# xduino_1_0.net
KiCad netlist of a schematic drawn in EAGLE
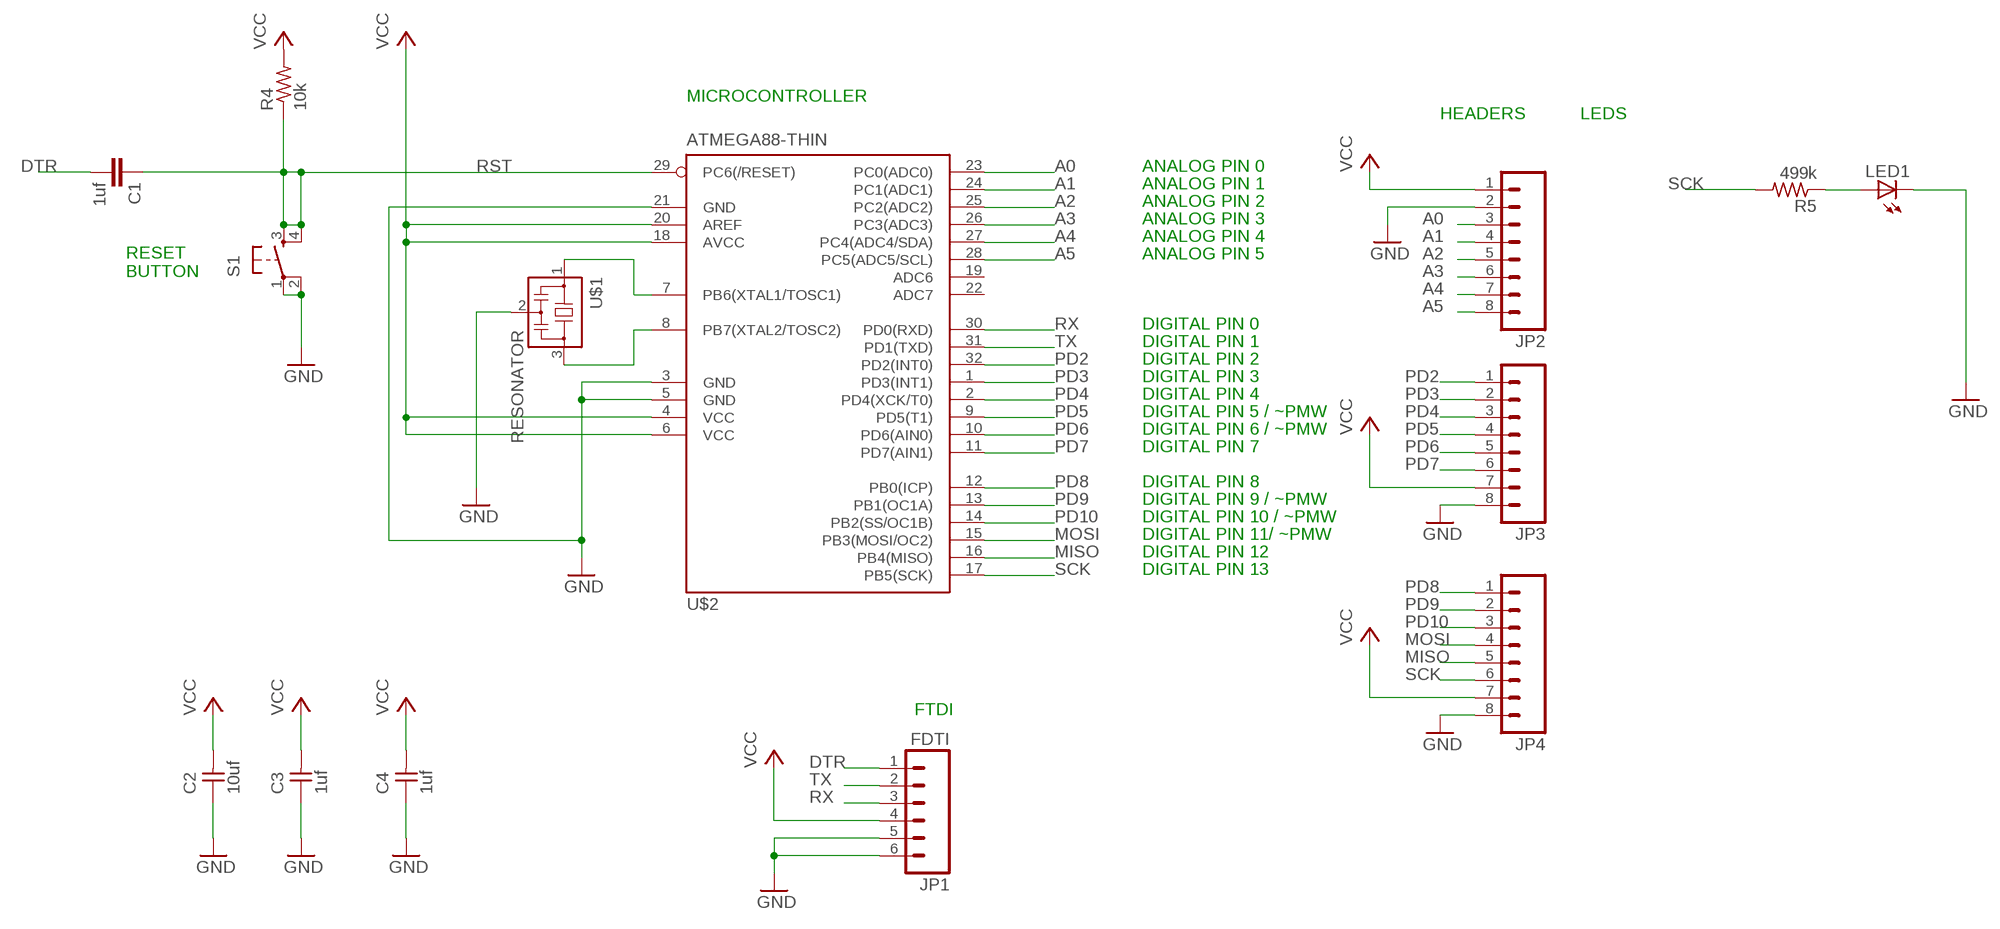
[diagram p0: schematic, sheet 1]

(export (version "E")
  (design (tool "Eeschema 10.0.6"))
  (components
    (comp (ref "C1")
      (value "1uf")
      (footprint "eagle-import:1206")
      (libsource (lib "eagle-import") (part "CAP1206"))
    )
    (comp (ref "C2")
      (value "10uf")
      (footprint "eagle-import:1206")
      (libsource (lib "eagle-import") (part "UNPOLARIZED_CAPACITOR1206"))
    )
    (comp (ref "C3")
      (value "1uf")
      (footprint "eagle-import:1206")
      (libsource (lib "eagle-import") (part "UNPOLARIZED_CAPACITOR1206"))
    )
    (comp (ref "C4")
      (value "1uf")
      (footprint "eagle-import:1206")
      (libsource (lib "eagle-import") (part "UNPOLARIZED_CAPACITOR1206"))
    )
    (comp (ref "JP1")
      (value "FDTI")
      (footprint "eagle-import:1X06-SMD_EDGE")
      (libsource (lib "eagle-import") (part "M061X06-SMD_EDGE_FEMALE"))
    )
    (comp (ref "JP2")
      (value "M08")
      (footprint "eagle-import:1X08")
      (libsource (lib "eagle-import") (part "M08"))
    )
    (comp (ref "JP3")
      (value "M08")
      (footprint "eagle-import:1X08")
      (libsource (lib "eagle-import") (part "M08"))
    )
    (comp (ref "JP4")
      (value "M08")
      (footprint "eagle-import:1X08")
      (libsource (lib "eagle-import") (part "M08"))
    )
    (comp (ref "LED1")
      (value "LED1206")
      (footprint "eagle-import:1206")
      (libsource (lib "eagle-import") (part "LED1206"))
    )
    (comp (ref "R4")
      (value "10k")
      (footprint "eagle-import:1206")
      (libsource (lib "eagle-import") (part "RESISTOR1206"))
    )
    (comp (ref "R5")
      (value "499k")
      (footprint "eagle-import:1206")
      (libsource (lib "eagle-import") (part "01_ng_RESISTOR1206"))
    )
    (comp (ref "S1")
      (value "6MM_SWITCH6MM_SWITCH")
      (footprint "eagle-import:6MM_SWITCH")
      (libsource (lib "eagle-import") (part "6MM_SWITCH6MM_SWITCH"))
    )
    (comp (ref "U$1")
      (value "RESONATOR")
      (footprint "eagle-import:EFOBM")
      (libsource (lib "eagle-import") (part "RESONATOR"))
    )
    (comp (ref "U$2")
      (value "ATMEGA88-THIN")
      (footprint "eagle-import:TQFP32-08THIN")
      (libsource (lib "eagle-import") (part "ATMEGA88-THIN"))
    )
  )
  (nets
    (net (code "1") (name "/A0") (class "Default")
      (node (ref "JP2") (pin "3") (pinfunction "3_3") (pintype "passive"))
      (node (ref "U$2") (pin "23") (pinfunction "PC0(ADC0)_23") (pintype "bidirectional"))
    )
    (net (code "2") (name "/A1") (class "Default")
      (node (ref "JP2") (pin "4") (pinfunction "4_4") (pintype "passive"))
      (node (ref "U$2") (pin "24") (pinfunction "PC1(ADC1)_24") (pintype "bidirectional"))
    )
    (net (code "3") (name "/A2") (class "Default")
      (node (ref "JP2") (pin "5") (pinfunction "5_5") (pintype "passive"))
      (node (ref "U$2") (pin "25") (pinfunction "PC2(ADC2)_25") (pintype "bidirectional"))
    )
    (net (code "4") (name "/A3") (class "Default")
      (node (ref "JP2") (pin "6") (pinfunction "6_6") (pintype "passive"))
      (node (ref "U$2") (pin "26") (pinfunction "PC3(ADC3)_26") (pintype "bidirectional"))
    )
    (net (code "5") (name "/A4") (class "Default")
      (node (ref "JP2") (pin "7") (pinfunction "7_7") (pintype "passive"))
      (node (ref "U$2") (pin "27") (pinfunction "PC4(ADC4/SDA)_27") (pintype "bidirectional"))
    )
    (net (code "6") (name "/A5") (class "Default")
      (node (ref "JP2") (pin "8") (pinfunction "8_8") (pintype "passive"))
      (node (ref "U$2") (pin "28") (pinfunction "PC5(ADC5/SCL)_28") (pintype "bidirectional"))
    )
    (net (code "7") (name "/DTR") (class "Default")
      (node (ref "C1") (pin "2") (pinfunction "2_2") (pintype "passive"))
      (node (ref "JP1") (pin "1") (pinfunction "1_1") (pintype "passive"))
    )
    (net (code "8") (name "/MISO") (class "Default")
      (node (ref "JP4") (pin "5") (pinfunction "5_5") (pintype "passive"))
      (node (ref "U$2") (pin "16") (pinfunction "PB4(MISO)_16") (pintype "bidirectional"))
    )
    (net (code "9") (name "/MOSI") (class "Default")
      (node (ref "JP4") (pin "4") (pinfunction "4_4") (pintype "passive"))
      (node (ref "U$2") (pin "15") (pinfunction "PB3(MOSI/OC2)_15") (pintype "bidirectional"))
    )
    (net (code "10") (name "/PD2") (class "Default")
      (node (ref "JP3") (pin "1") (pinfunction "1_1") (pintype "passive"))
      (node (ref "U$2") (pin "32") (pinfunction "PD2(INT0)_32") (pintype "bidirectional"))
    )
    (net (code "11") (name "/PD3") (class "Default")
      (node (ref "JP3") (pin "2") (pinfunction "2_2") (pintype "passive"))
      (node (ref "U$2") (pin "1") (pinfunction "PD3(INT1)_1") (pintype "bidirectional"))
    )
    (net (code "12") (name "/PD4") (class "Default")
      (node (ref "JP3") (pin "3") (pinfunction "3_3") (pintype "passive"))
      (node (ref "U$2") (pin "2") (pinfunction "PD4(XCK/T0)_2") (pintype "bidirectional"))
    )
    (net (code "13") (name "/PD5") (class "Default")
      (node (ref "JP3") (pin "4") (pinfunction "4_4") (pintype "passive"))
      (node (ref "U$2") (pin "9") (pinfunction "PD5(T1)_9") (pintype "bidirectional"))
    )
    (net (code "14") (name "/PD6") (class "Default")
      (node (ref "JP3") (pin "5") (pinfunction "5_5") (pintype "passive"))
      (node (ref "U$2") (pin "10") (pinfunction "PD6(AIN0)_10") (pintype "bidirectional"))
    )
    (net (code "15") (name "/PD7") (class "Default")
      (node (ref "JP3") (pin "6") (pinfunction "6_6") (pintype "passive"))
      (node (ref "U$2") (pin "11") (pinfunction "PD7(AIN1)_11") (pintype "bidirectional"))
    )
    (net (code "16") (name "/PD8") (class "Default")
      (node (ref "JP4") (pin "1") (pinfunction "1_1") (pintype "passive"))
      (node (ref "U$2") (pin "12") (pinfunction "PB0(ICP)_12") (pintype "bidirectional"))
    )
    (net (code "17") (name "/PD9") (class "Default")
      (node (ref "JP4") (pin "2") (pinfunction "2_2") (pintype "passive"))
      (node (ref "U$2") (pin "13") (pinfunction "PB1(OC1A)_13") (pintype "bidirectional"))
    )
    (net (code "18") (name "/PD10") (class "Default")
      (node (ref "JP4") (pin "3") (pinfunction "3_3") (pintype "passive"))
      (node (ref "U$2") (pin "14") (pinfunction "PB2(SS/OC1B)_14") (pintype "bidirectional"))
    )
    (net (code "19") (name "/RST") (class "Default")
      (node (ref "C1") (pin "1") (pinfunction "1_1") (pintype "passive"))
      (node (ref "R4") (pin "1") (pinfunction "1_1") (pintype "passive"))
      (node (ref "S1") (pin "3") (pinfunction "S_3") (pintype "passive"))
      (node (ref "S1") (pin "4") (pinfunction "S1_4") (pintype "passive"))
      (node (ref "U$2") (pin "29") (pinfunction "PC6(/RESET)_29") (pintype "bidirectional"))
    )
    (net (code "20") (name "/RX") (class "Default")
      (node (ref "JP1") (pin "3") (pinfunction "3_3") (pintype "passive"))
      (node (ref "U$2") (pin "30") (pinfunction "PD0(RXD)_30") (pintype "bidirectional"))
    )
    (net (code "21") (name "/SCK") (class "Default")
      (node (ref "JP4") (pin "6") (pinfunction "6_6") (pintype "passive"))
      (node (ref "R5") (pin "2") (pinfunction "2_2") (pintype "passive"))
      (node (ref "U$2") (pin "17") (pinfunction "PB5(SCK)_17") (pintype "bidirectional"))
    )
    (net (code "22") (name "/TX") (class "Default")
      (node (ref "JP1") (pin "2") (pinfunction "2_2") (pintype "passive"))
      (node (ref "U$2") (pin "31") (pinfunction "PD1(TXD)_31") (pintype "bidirectional"))
    )
    (net (code "23") (name "GND") (class "Default")
      (node (ref "C2") (pin "1") (pinfunction "1_1") (pintype "passive"))
      (node (ref "C3") (pin "1") (pinfunction "1_1") (pintype "passive"))
      (node (ref "C4") (pin "1") (pinfunction "1_1") (pintype "passive"))
      (node (ref "JP1") (pin "5") (pinfunction "5_5") (pintype "passive"))
      (node (ref "JP1") (pin "6") (pinfunction "6_6") (pintype "passive"))
      (node (ref "JP2") (pin "2") (pinfunction "2_2") (pintype "passive"))
      (node (ref "JP3") (pin "8") (pinfunction "8_8") (pintype "passive"))
      (node (ref "JP4") (pin "8") (pinfunction "8_8") (pintype "passive"))
      (node (ref "LED1") (pin "2") (pinfunction "C_2") (pintype "passive"))
      (node (ref "S1") (pin "1") (pinfunction "P_1") (pintype "passive"))
      (node (ref "S1") (pin "2") (pinfunction "P1_2") (pintype "passive"))
      (node (ref "U$1") (pin "2") (pinfunction "2_2") (pintype "passive"))
      (node (ref "U$2") (pin "21") (pinfunction "GND_21") (pintype "power_in"))
      (node (ref "U$2") (pin "3") (pinfunction "GND_3") (pintype "power_in"))
      (node (ref "U$2") (pin "5") (pinfunction "GND_5") (pintype "power_in"))
    )
    (net (code "24") (name "Net-(LED1-A)") (class "Default")
      (node (ref "LED1") (pin "1") (pinfunction "A_1") (pintype "passive"))
      (node (ref "R5") (pin "1") (pinfunction "1_1") (pintype "passive"))
    )
    (net (code "25") (name "Net-(U$2-PB6(XTAL1{slash}TOSC1))") (class "Default")
      (node (ref "U$1") (pin "1") (pinfunction "1_1") (pintype "passive"))
      (node (ref "U$2") (pin "7") (pinfunction "PB6(XTAL1/TOSC1)_7") (pintype "bidirectional"))
    )
    (net (code "26") (name "Net-(U$2-PB7(XTAL2{slash}TOSC2))") (class "Default")
      (node (ref "U$1") (pin "3") (pinfunction "3_3") (pintype "passive"))
      (node (ref "U$2") (pin "8") (pinfunction "PB7(XTAL2/TOSC2)_8") (pintype "bidirectional"))
    )
    (net (code "27") (name "VCC") (class "Default")
      (node (ref "C2") (pin "2") (pinfunction "2_2") (pintype "passive"))
      (node (ref "C3") (pin "2") (pinfunction "2_2") (pintype "passive"))
      (node (ref "C4") (pin "2") (pinfunction "2_2") (pintype "passive"))
      (node (ref "JP1") (pin "4") (pinfunction "4_4") (pintype "passive"))
      (node (ref "JP2") (pin "1") (pinfunction "1_1") (pintype "passive"))
      (node (ref "JP3") (pin "7") (pinfunction "7_7") (pintype "passive"))
      (node (ref "JP4") (pin "7") (pinfunction "7_7") (pintype "passive"))
      (node (ref "R4") (pin "2") (pinfunction "2_2") (pintype "passive"))
      (node (ref "U$2") (pin "18") (pinfunction "AVCC_18") (pintype "power_in"))
      (node (ref "U$2") (pin "20") (pinfunction "AREF_20") (pintype "passive"))
      (node (ref "U$2") (pin "4") (pinfunction "VCC_4") (pintype "power_in"))
      (node (ref "U$2") (pin "6") (pinfunction "VCC_6") (pintype "power_in"))
    )
    (net (code "28") (name "unconnected-(U$2-ADC6-Pad19)") (class "Default")
      (node (ref "U$2") (pin "19") (pinfunction "ADC6_19") (pintype "bidirectional"))
    )
    (net (code "29") (name "unconnected-(U$2-ADC7-Pad22)") (class "Default")
      (node (ref "U$2") (pin "22") (pinfunction "ADC7_22") (pintype "bidirectional"))
    )
  )
)
